# ANN.net
KiCad netlist of a schematic drawn in Altium Designer
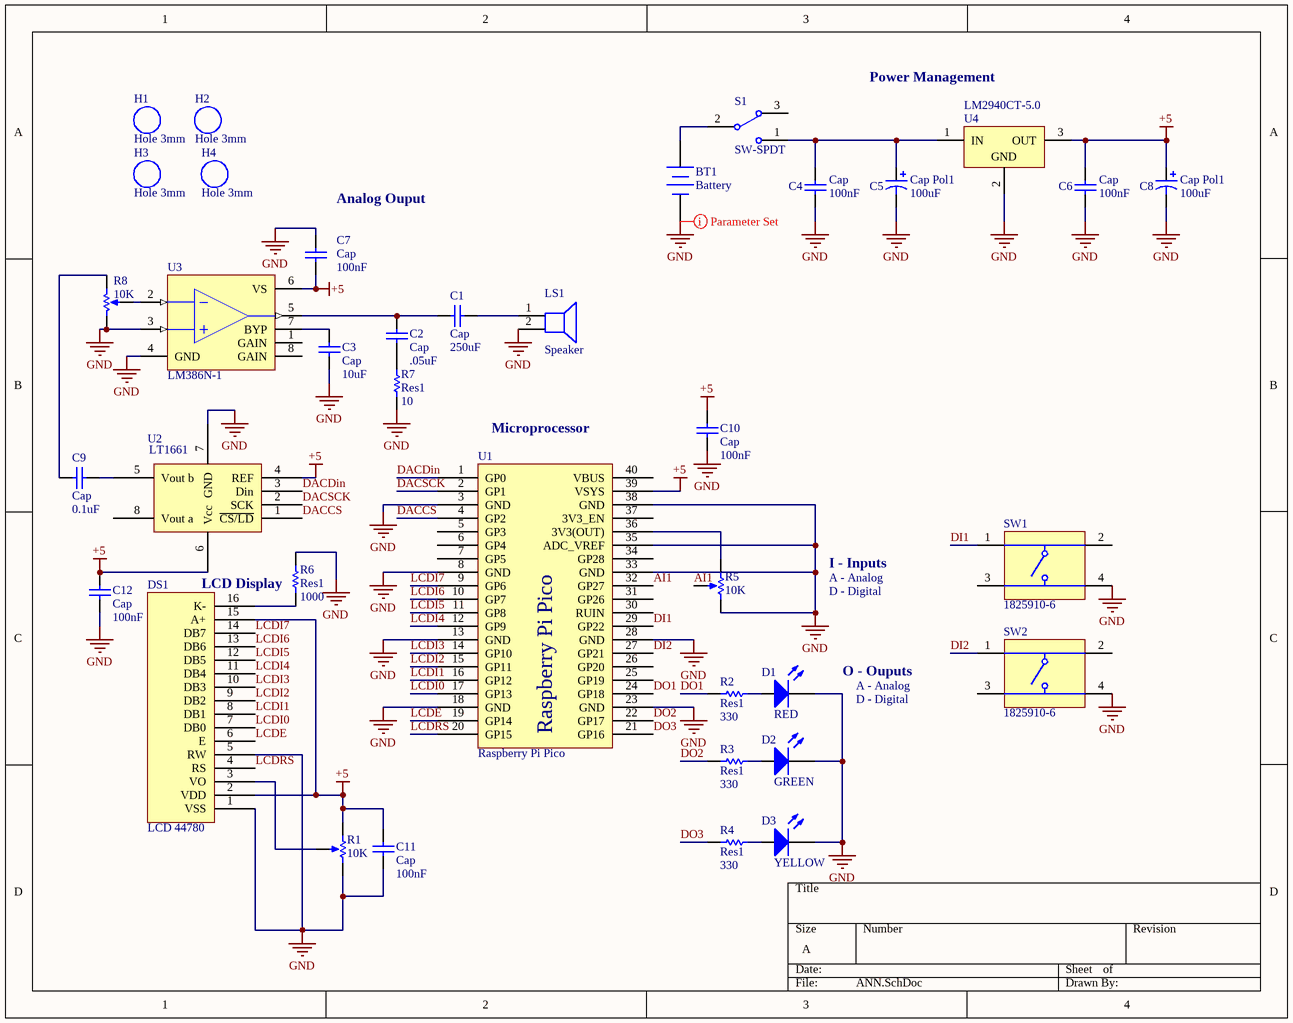
[diagram p0: ANN.SchDoc]

(export (version "E")
  (design (tool "Eeschema 10.0.6"))
  (components
    (comp (ref "BT1")
      (value "Battery")
      (footprint "BAT-2")
      (description "Multicell Battery")
      (fields (field (name "PUBLISHER") "Altium Limited"))
      (libsource (lib "Miscellaneous Devices") (part "Battery"))
    )
    (comp (ref "C1")
      (value "Cap")
      (footprint "RAD-0.3")
      (description "Capacitor")
      (fields (field (name "ALTIUM_VALUE") "250uF") (field (name "PUBLISHER") "Altium Limited"))
      (libsource (lib "Miscellaneous Devices") (part "Cap"))
    )
    (comp (ref "C2")
      (value "Cap")
      (footprint "RAD-0.3")
      (description "Capacitor")
      (fields (field (name "ALTIUM_VALUE") ".05uF") (field (name "PUBLISHER") "Altium Limited"))
      (libsource (lib "Miscellaneous Devices") (part "Cap"))
    )
    (comp (ref "C3")
      (value "Cap")
      (footprint "RAD-0.3")
      (description "Capacitor")
      (fields (field (name "ALTIUM_VALUE") "10uF") (field (name "PUBLISHER") "Altium Limited"))
      (libsource (lib "Miscellaneous Devices") (part "Cap"))
    )
    (comp (ref "C4")
      (value "Cap")
      (footprint "RAD-0.3")
      (description "Capacitor")
      (fields (field (name "ALTIUM_VALUE") "100nF") (field (name "PUBLISHER") "Altium Limited"))
      (libsource (lib "Miscellaneous Devices") (part "Cap"))
    )
    (comp (ref "C5")
      (value "Cap Pol1")
      (footprint "RB7.6-15")
      (description "Polarized Capacitor (Radial)")
      (fields (field (name "ALTIUM_VALUE") "100uF") (field (name "PUBLISHER") "Altium Limited"))
      (libsource (lib "Miscellaneous Devices") (part "Cap Pol1"))
    )
    (comp (ref "C6")
      (value "Cap")
      (footprint "RAD-0.3")
      (description "Capacitor")
      (fields (field (name "ALTIUM_VALUE") "100nF") (field (name "PUBLISHER") "Altium Limited"))
      (libsource (lib "Miscellaneous Devices") (part "Cap"))
    )
    (comp (ref "C7")
      (value "Cap")
      (footprint "RAD-0.3")
      (description "Capacitor")
      (fields (field (name "ALTIUM_VALUE") "100nF") (field (name "PUBLISHER") "Altium Limited"))
      (libsource (lib "Miscellaneous Devices") (part "Cap"))
    )
    (comp (ref "C8")
      (value "Cap Pol1")
      (footprint "RB7.6-15")
      (description "Polarized Capacitor (Radial)")
      (fields (field (name "ALTIUM_VALUE") "100uF") (field (name "PUBLISHER") "Altium Limited"))
      (libsource (lib "Miscellaneous Devices") (part "Cap Pol1"))
    )
    (comp (ref "C9")
      (value "Cap")
      (footprint "RAD-0.3")
      (description "Capacitor")
      (fields (field (name "ALTIUM_VALUE") "0.1uF") (field (name "PUBLISHER") "Altium Limited"))
      (libsource (lib "Miscellaneous Devices") (part "Cap"))
    )
    (comp (ref "C10")
      (value "Cap")
      (footprint "RAD-0.3")
      (description "Capacitor")
      (fields (field (name "ALTIUM_VALUE") "100nF") (field (name "PUBLISHER") "Altium Limited"))
      (libsource (lib "Miscellaneous Devices") (part "Cap"))
    )
    (comp (ref "C11")
      (value "Cap")
      (footprint "RAD-0.3")
      (description "Capacitor")
      (fields (field (name "ALTIUM_VALUE") "100nF") (field (name "PUBLISHER") "Altium Limited"))
      (libsource (lib "Miscellaneous Devices") (part "Cap"))
    )
    (comp (ref "C12")
      (value "Cap")
      (footprint "RAD-0.3")
      (description "Capacitor")
      (fields (field (name "ALTIUM_VALUE") "100nF") (field (name "PUBLISHER") "Altium Limited"))
      (libsource (lib "Miscellaneous Devices") (part "Cap"))
    )
    (comp (ref "D1")
      (value "RED")
      (footprint "LED-0")
      (description "Typical INFRARED GaAs LED")
      (fields (field (name "PUBLISHER") "Altium Limited"))
      (libsource (lib "Miscellaneous Devices") (part "LED0"))
    )
    (comp (ref "D2")
      (value "GREEN")
      (footprint "LED-0")
      (description "Typical INFRARED GaAs LED")
      (fields (field (name "PUBLISHER") "Altium Limited"))
      (libsource (lib "Miscellaneous Devices") (part "LED0"))
    )
    (comp (ref "D3")
      (value "YELLOW")
      (footprint "LED-0")
      (description "Typical INFRARED GaAs LED")
      (fields (field (name "PUBLISHER") "Altium Limited"))
      (libsource (lib "Miscellaneous Devices") (part "LED0"))
    )
    (comp (ref "DS1")
      (value "LCD 44780")
      (footprint "OLED 16x2")
      (libsource (lib "ECE Lib 22") (part "LCD 44780"))
    )
    (comp (ref "H1")
      (value "Hole 3mm")
      (footprint "Hole 3mm")
      (libsource (lib "ECE Lib 22") (part "Hole 3mm"))
    )
    (comp (ref "H2")
      (value "Hole 3mm")
      (footprint "Hole 3mm")
      (libsource (lib "ECE Lib 22") (part "Hole 3mm"))
    )
    (comp (ref "H3")
      (value "Hole 3mm")
      (footprint "Hole 3mm")
      (libsource (lib "ECE Lib 22") (part "Hole 3mm"))
    )
    (comp (ref "H4")
      (value "Hole 3mm")
      (footprint "Hole 3mm")
      (libsource (lib "ECE Lib 22") (part "Hole 3mm"))
    )
    (comp (ref "LS1")
      (value "Speaker")
      (footprint "PIN2")
      (description "Loudspeaker")
      (fields (field (name "PUBLISHER") "Altium Limited"))
      (libsource (lib "Miscellaneous Devices") (part "Speaker"))
    )
    (comp (ref "R1")
      (value "10K")
      (footprint "POT OFFSET 100_1")
      (description "Potentiometer")
      (fields (field (name "Comment") "RPot_2") (field (name "PUBLISHER") "Altium Limited"))
      (libsource (lib "ECE LIB new") (part "RPot_5"))
    )
    (comp (ref "R2")
      (value "Res1")
      (footprint "AXIAL-0.3")
      (description "Resistor")
      (fields (field (name "ALTIUM_VALUE") "330") (field (name "PUBLISHER") "Altium Limited"))
      (libsource (lib "Miscellaneous Devices") (part "Res1"))
    )
    (comp (ref "R3")
      (value "Res1")
      (footprint "AXIAL-0.3")
      (description "Resistor")
      (fields (field (name "ALTIUM_VALUE") "330") (field (name "PUBLISHER") "Altium Limited"))
      (libsource (lib "Miscellaneous Devices") (part "Res1"))
    )
    (comp (ref "R4")
      (value "Res1")
      (footprint "AXIAL-0.3")
      (description "Resistor")
      (fields (field (name "ALTIUM_VALUE") "330") (field (name "PUBLISHER") "Altium Limited"))
      (libsource (lib "Miscellaneous Devices") (part "Res1"))
    )
    (comp (ref "R5")
      (value "10K")
      (footprint "POT OFFSET 100_1")
      (description "Potentiometer")
      (fields (field (name "Comment") "RPot_2") (field (name "PUBLISHER") "Altium Limited"))
      (libsource (lib "ECE LIB new") (part "RPot_5"))
    )
    (comp (ref "R6")
      (value "Res1")
      (footprint "AXIAL-0.3")
      (description "Resistor")
      (fields (field (name "ALTIUM_VALUE") "1000") (field (name "PUBLISHER") "Altium Limited"))
      (libsource (lib "Miscellaneous Devices") (part "Res1"))
    )
    (comp (ref "R7")
      (value "Res1")
      (footprint "AXIAL-0.3")
      (description "Resistor")
      (fields (field (name "ALTIUM_VALUE") "10") (field (name "PUBLISHER") "Altium Limited"))
      (libsource (lib "Miscellaneous Devices") (part "Res1"))
    )
    (comp (ref "R8")
      (value "10K")
      (footprint "POT OFFSET 100_1")
      (description "Potentiometer")
      (fields (field (name "Comment") "RPot_2") (field (name "PUBLISHER") "Altium Limited"))
      (libsource (lib "ECE LIB new") (part "RPot_5"))
    )
    (comp (ref "S1")
      (value "SW-SPDT")
      (footprint "SW DPST jameco")
      (description "SPDT Subminiature Toggle Switch, Right Angle Mounting, Vertical Actuation")
      (fields (field (name "PUBLISHER") "Altium Limited"))
      (libsource (lib "ECE Lib 22") (part "SW-SPDT"))
    )
    (comp (ref "SW1")
      (value "1825910-6")
      (footprint "TECO-1825910-6_V")
      (description "Tact Switch, SPST-NO, 0.05 A, -35 to 85 degC, 4-Pin THD, RoHS, Bulk")
      (fields (field (name "MANUFACTURER") "TE Connectivity"))
      (libsource (lib "Altium Content Vault") (part "SW-SPST-4_A"))
    )
    (comp (ref "SW2")
      (value "1825910-6")
      (footprint "TECO-1825910-6_V")
      (description "Tact Switch, SPST-NO, 0.05 A, -35 to 85 degC, 4-Pin THD, RoHS, Bulk")
      (fields (field (name "MANUFACTURER") "TE Connectivity"))
      (libsource (lib "Altium Content Vault") (part "SW-SPST-4_A"))
    )
    (comp (ref "U1")
      (value "Raspberry Pi Pico")
      (footprint "Raspberry Pi Pico")
      (libsource (lib "ECE Lib 22") (part "Raspberry Pi Pico"))
    )
    (comp (ref "U2") (value "LT1661") (footprint "DIP-8") (libsource (lib "ECE LIB new") (part "LT1661")))
    (comp (ref "U3")
      (value "LM386N-1")
      (footprint "DIP-8")
      (description "Low-Voltage Audio Power Amplifier")
      (fields (field (name "PUBLISHER") "Altium Limited"))
      (libsource (lib "ECE LIB new") (part "LM386N-1"))
    )
    (comp (ref "U4")
      (value "LM2940CT-5.0")
      (footprint "T03B")
      (description "1A Low Dropout Regulator, 3-pin TO-220")
      (fields (field (name "MANUFACTURER") "National Semiconductor"))
      (libsource (lib "ECE Lib 22") (part "LM2940CT-5.0_1"))
    )
  )
  (nets
    (net (code "1") (name "+5") (class "Default")
      (node (ref "C10") (pin "2") (pinfunction "2_2") (pintype "passive"))
      (node (ref "C11") (pin "2") (pinfunction "2_2") (pintype "passive"))
      (node (ref "C12") (pin "2") (pinfunction "2_2") (pintype "passive"))
      (node (ref "C6") (pin "2") (pinfunction "2_2") (pintype "passive"))
      (node (ref "C7") (pin "2") (pinfunction "2_2") (pintype "passive"))
      (node (ref "C8") (pin "1") (pinfunction "1_1") (pintype "passive"))
      (node (ref "DS1") (pin "15") (pinfunction "A+_15") (pintype "passive"))
      (node (ref "DS1") (pin "2") (pinfunction "VDD_2") (pintype "passive"))
      (node (ref "R1") (pin "1") (pinfunction "TOP_1") (pintype "passive"))
      (node (ref "U1") (pin "39") (pinfunction "VSYS_39") (pintype "passive"))
      (node (ref "U2") (pin "4") (pinfunction "REF_4") (pintype "passive"))
      (node (ref "U2") (pin "6") (pinfunction "Vcc_6") (pintype "passive"))
      (node (ref "U3") (pin "6") (pinfunction "VS_6") (pintype "power_in"))
      (node (ref "U4") (pin "3") (pinfunction "OUT_3") (pintype "power_in"))
    )
    (net (code "2") (name "/AI1") (class "Default")
      (node (ref "R5") (pin "2") (pinfunction "TAP_2") (pintype "passive"))
      (node (ref "U1") (pin "32") (pinfunction "GP27_32") (pintype "passive"))
    )
    (net (code "3") (name "/DACCS") (class "Default")
      (node (ref "U1") (pin "4") (pinfunction "GP2_4") (pintype "passive"))
      (node (ref "U2") (pin "1") (pinfunction "~{CS/LD}_1") (pintype "passive"))
    )
    (net (code "4") (name "/DACDin") (class "Default")
      (node (ref "U1") (pin "1") (pinfunction "GP0_1") (pintype "passive"))
      (node (ref "U2") (pin "3") (pinfunction "Din_3") (pintype "passive"))
    )
    (net (code "5") (name "/DACSCK") (class "Default")
      (node (ref "U1") (pin "2") (pinfunction "GP1_2") (pintype "passive"))
      (node (ref "U2") (pin "2") (pinfunction "SCK_2") (pintype "passive"))
    )
    (net (code "6") (name "/DI1") (class "Default")
      (node (ref "SW1") (pin "1") (pinfunction "1_1") (pintype "passive"))
      (node (ref "U1") (pin "29") (pinfunction "GP22_29") (pintype "passive"))
    )
    (net (code "7") (name "/DI2") (class "Default")
      (node (ref "SW2") (pin "1") (pinfunction "1_1") (pintype "passive"))
      (node (ref "U1") (pin "27") (pinfunction "GP21_27") (pintype "passive"))
    )
    (net (code "8") (name "/DO1") (class "Default")
      (node (ref "R2") (pin "1") (pinfunction "1_1") (pintype "passive"))
      (node (ref "U1") (pin "24") (pinfunction "GP18_24") (pintype "passive"))
    )
    (net (code "9") (name "/DO2") (class "Default")
      (node (ref "R3") (pin "1") (pinfunction "1_1") (pintype "passive"))
      (node (ref "U1") (pin "22") (pinfunction "GP17_22") (pintype "passive"))
    )
    (net (code "10") (name "/DO3") (class "Default")
      (node (ref "R4") (pin "1") (pinfunction "1_1") (pintype "passive"))
      (node (ref "U1") (pin "21") (pinfunction "GP16_21") (pintype "passive"))
    )
    (net (code "11") (name "/LCDE") (class "Default")
      (node (ref "DS1") (pin "6") (pinfunction "E_6") (pintype "passive"))
      (node (ref "U1") (pin "19") (pinfunction "GP14_19") (pintype "passive"))
    )
    (net (code "12") (name "/LCDI0") (class "Default")
      (node (ref "DS1") (pin "7") (pinfunction "DB0_7") (pintype "passive"))
      (node (ref "U1") (pin "17") (pinfunction "GP13_17") (pintype "passive"))
    )
    (net (code "13") (name "/LCDI1") (class "Default")
      (node (ref "DS1") (pin "8") (pinfunction "DB1_8") (pintype "passive"))
      (node (ref "U1") (pin "16") (pinfunction "GP12_16") (pintype "passive"))
    )
    (net (code "14") (name "/LCDI2") (class "Default")
      (node (ref "DS1") (pin "9") (pinfunction "DB2_9") (pintype "passive"))
      (node (ref "U1") (pin "15") (pinfunction "GP11_15") (pintype "passive"))
    )
    (net (code "15") (name "/LCDI3") (class "Default")
      (node (ref "DS1") (pin "10") (pinfunction "DB3_10") (pintype "passive"))
      (node (ref "U1") (pin "14") (pinfunction "GP10_14") (pintype "passive"))
    )
    (net (code "16") (name "/LCDI4") (class "Default")
      (node (ref "DS1") (pin "11") (pinfunction "DB4_11") (pintype "passive"))
      (node (ref "U1") (pin "12") (pinfunction "GP9_12") (pintype "passive"))
    )
    (net (code "17") (name "/LCDI5") (class "Default")
      (node (ref "DS1") (pin "12") (pinfunction "DB5_12") (pintype "passive"))
      (node (ref "U1") (pin "11") (pinfunction "GP8_11") (pintype "passive"))
    )
    (net (code "18") (name "/LCDI6") (class "Default")
      (node (ref "DS1") (pin "13") (pinfunction "DB6_13") (pintype "passive"))
      (node (ref "U1") (pin "10") (pinfunction "GP7_10") (pintype "passive"))
    )
    (net (code "19") (name "/LCDI7") (class "Default")
      (node (ref "DS1") (pin "14") (pinfunction "DB7_14") (pintype "passive"))
      (node (ref "U1") (pin "9") (pinfunction "GP6_9") (pintype "passive"))
    )
    (net (code "20") (name "/LCDRS") (class "Default")
      (node (ref "DS1") (pin "4") (pinfunction "RS_4") (pintype "passive"))
      (node (ref "U1") (pin "20") (pinfunction "GP15_20") (pintype "passive"))
    )
    (net (code "21") (name "GND") (class "Default")
      (node (ref "BT1") (pin "2") (pinfunction "-_2") (pintype "passive"))
      (node (ref "C10") (pin "1") (pinfunction "1_1") (pintype "passive"))
      (node (ref "C11") (pin "1") (pinfunction "1_1") (pintype "passive"))
      (node (ref "C12") (pin "1") (pinfunction "1_1") (pintype "passive"))
      (node (ref "C3") (pin "1") (pinfunction "1_1") (pintype "passive"))
      (node (ref "C4") (pin "1") (pinfunction "1_1") (pintype "passive"))
      (node (ref "C5") (pin "2") (pinfunction "2_2") (pintype "passive"))
      (node (ref "C6") (pin "1") (pinfunction "1_1") (pintype "passive"))
      (node (ref "C7") (pin "1") (pinfunction "1_1") (pintype "passive"))
      (node (ref "C8") (pin "2") (pinfunction "2_2") (pintype "passive"))
      (node (ref "D1") (pin "2") (pinfunction "K_2") (pintype "passive"))
      (node (ref "D2") (pin "2") (pinfunction "K_2") (pintype "passive"))
      (node (ref "D3") (pin "2") (pinfunction "K_2") (pintype "passive"))
      (node (ref "DS1") (pin "1") (pinfunction "VSS_1") (pintype "passive"))
      (node (ref "DS1") (pin "5") (pinfunction "RW_5") (pintype "passive"))
      (node (ref "LS1") (pin "2") (pinfunction "2_2") (pintype "passive"))
      (node (ref "R1") (pin "3") (pinfunction "BOT_3") (pintype "passive"))
      (node (ref "R5") (pin "3") (pinfunction "BOT_3") (pintype "passive"))
      (node (ref "R6") (pin "2") (pinfunction "2_2") (pintype "passive"))
      (node (ref "R7") (pin "1") (pinfunction "1_1") (pintype "passive"))
      (node (ref "R8") (pin "3") (pinfunction "BOT_3") (pintype "passive"))
      (node (ref "SW1") (pin "4") (pinfunction "4_4") (pintype "passive"))
      (node (ref "SW2") (pin "4") (pinfunction "4_4") (pintype "passive"))
      (node (ref "U1") (pin "13") (pinfunction "GND_13") (pintype "passive"))
      (node (ref "U1") (pin "18") (pinfunction "GND_18") (pintype "passive"))
      (node (ref "U1") (pin "23") (pinfunction "GND_23") (pintype "passive"))
      (node (ref "U1") (pin "28") (pinfunction "GND_28") (pintype "passive"))
      (node (ref "U1") (pin "3") (pinfunction "GND_3") (pintype "passive"))
      (node (ref "U1") (pin "33") (pinfunction "GND_33") (pintype "passive"))
      (node (ref "U1") (pin "35") (pinfunction "ADC_VREF_35") (pintype "passive"))
      (node (ref "U1") (pin "38") (pinfunction "GND_38") (pintype "passive"))
      (node (ref "U1") (pin "8") (pinfunction "GND_8") (pintype "passive"))
      (node (ref "U2") (pin "7") (pinfunction "GND_7") (pintype "passive"))
      (node (ref "U3") (pin "3") (pinfunction "IN+_3") (pintype "input"))
      (node (ref "U3") (pin "4") (pinfunction "GND_4") (pintype "power_in"))
      (node (ref "U4") (pin "2") (pinfunction "GND_2") (pintype "power_in"))
    )
    (net (code "22") (name "Net-(BT1-+)") (class "Default")
      (node (ref "BT1") (pin "1") (pinfunction "+_1") (pintype "passive"))
      (node (ref "S1") (pin "2") (pinfunction "2_2") (pintype "passive"))
    )
    (net (code "23") (name "Net-(C1-Pad1)") (class "Default")
      (node (ref "C1") (pin "1") (pinfunction "1_1") (pintype "passive"))
      (node (ref "LS1") (pin "1") (pinfunction "1_1") (pintype "passive"))
    )
    (net (code "24") (name "Net-(C2-Pad1)") (class "Default")
      (node (ref "C2") (pin "1") (pinfunction "1_1") (pintype "passive"))
      (node (ref "R7") (pin "2") (pinfunction "2_2") (pintype "passive"))
    )
    (net (code "25") (name "Net-(D1-A)") (class "Default")
      (node (ref "D1") (pin "1") (pinfunction "A_1") (pintype "passive"))
      (node (ref "R2") (pin "2") (pinfunction "2_2") (pintype "passive"))
    )
    (net (code "26") (name "Net-(D2-A)") (class "Default")
      (node (ref "D2") (pin "1") (pinfunction "A_1") (pintype "passive"))
      (node (ref "R3") (pin "2") (pinfunction "2_2") (pintype "passive"))
    )
    (net (code "27") (name "Net-(D3-A)") (class "Default")
      (node (ref "D3") (pin "1") (pinfunction "A_1") (pintype "passive"))
      (node (ref "R4") (pin "2") (pinfunction "2_2") (pintype "passive"))
    )
    (net (code "28") (name "Net-(DS1-K-)") (class "Default")
      (node (ref "DS1") (pin "16") (pinfunction "K-_16") (pintype "passive"))
      (node (ref "R6") (pin "1") (pinfunction "1_1") (pintype "passive"))
    )
    (net (code "29") (name "Net-(DS1-VO)") (class "Default")
      (node (ref "DS1") (pin "3") (pinfunction "VO_3") (pintype "passive"))
      (node (ref "R1") (pin "2") (pinfunction "TAP_2") (pintype "passive"))
    )
    (net (code "30") (name "Net-(R5-TOP)") (class "Default")
      (node (ref "R5") (pin "1") (pinfunction "TOP_1") (pintype "passive"))
      (node (ref "U1") (pin "36") (pinfunction "3V3(OUT)_36") (pintype "passive"))
    )
    (net (code "31") (name "Net-(R8-TAP)") (class "Default")
      (node (ref "R8") (pin "2") (pinfunction "TAP_2") (pintype "passive"))
      (node (ref "U3") (pin "2") (pinfunction "IN-_2") (pintype "input"))
    )
    (net (code "32") (name "Net-(R8-TOP)") (class "Default")
      (node (ref "C9") (pin "2") (pinfunction "2_2") (pintype "passive"))
      (node (ref "R8") (pin "1") (pinfunction "TOP_1") (pintype "passive"))
    )
    (net (code "33") (name "Net-(U2-Vout_b)") (class "Default")
      (node (ref "C9") (pin "1") (pinfunction "1_1") (pintype "passive"))
      (node (ref "U2") (pin "5") (pinfunction "Vout_b_5") (pintype "passive"))
    )
    (net (code "34") (name "Net-(U3-BYP)") (class "Default")
      (node (ref "C3") (pin "2") (pinfunction "2_2") (pintype "passive"))
      (node (ref "U3") (pin "7") (pinfunction "BYP_7") (pintype "passive"))
    )
    (net (code "35") (name "Net-(U3-OUT)") (class "Default")
      (node (ref "C1") (pin "2") (pinfunction "2_2") (pintype "passive"))
      (node (ref "C2") (pin "2") (pinfunction "2_2") (pintype "passive"))
      (node (ref "U3") (pin "5") (pinfunction "OUT_5") (pintype "output"))
    )
    (net (code "36") (name "Net-(U4-IN)") (class "Default")
      (node (ref "C4") (pin "2") (pinfunction "2_2") (pintype "passive"))
      (node (ref "C5") (pin "1") (pinfunction "1_1") (pintype "passive"))
      (node (ref "S1") (pin "1") (pinfunction "1_1") (pintype "passive"))
      (node (ref "U4") (pin "1") (pinfunction "IN_1") (pintype "power_in"))
    )
    (net (code "37") (name "unconnected-(S1-Pad3)") (class "Default")
      (node (ref "S1") (pin "3") (pinfunction "3_3") (pintype "passive"))
    )
    (net (code "38") (name "unconnected-(SW1-Pad2)") (class "Default")
      (node (ref "SW1") (pin "2") (pinfunction "2_2") (pintype "passive"))
    )
    (net (code "39") (name "unconnected-(SW1-Pad3)") (class "Default")
      (node (ref "SW1") (pin "3") (pinfunction "3_3") (pintype "passive"))
    )
    (net (code "40") (name "unconnected-(SW2-Pad2)") (class "Default")
      (node (ref "SW2") (pin "2") (pinfunction "2_2") (pintype "passive"))
    )
    (net (code "41") (name "unconnected-(SW2-Pad3)") (class "Default")
      (node (ref "SW2") (pin "3") (pinfunction "3_3") (pintype "passive"))
    )
    (net (code "42") (name "unconnected-(U1-3V3_EN-Pad37)") (class "Default")
      (node (ref "U1") (pin "37") (pinfunction "3V3_EN_37") (pintype "passive"))
    )
    (net (code "43") (name "unconnected-(U1-GP3-Pad5)") (class "Default")
      (node (ref "U1") (pin "5") (pinfunction "GP3_5") (pintype "passive"))
    )
    (net (code "44") (name "unconnected-(U1-GP4-Pad6)") (class "Default")
      (node (ref "U1") (pin "6") (pinfunction "GP4_6") (pintype "passive"))
    )
    (net (code "45") (name "unconnected-(U1-GP5-Pad7)") (class "Default")
      (node (ref "U1") (pin "7") (pinfunction "GP5_7") (pintype "passive"))
    )
    (net (code "46") (name "unconnected-(U1-GP19-Pad25)") (class "Default")
      (node (ref "U1") (pin "25") (pinfunction "GP19_25") (pintype "passive"))
    )
    (net (code "47") (name "unconnected-(U1-GP20-Pad26)") (class "Default")
      (node (ref "U1") (pin "26") (pinfunction "GP20_26") (pintype "passive"))
    )
    (net (code "48") (name "unconnected-(U1-GP26-Pad31)") (class "Default")
      (node (ref "U1") (pin "31") (pinfunction "GP26_31") (pintype "passive"))
    )
    (net (code "49") (name "unconnected-(U1-GP28-Pad34)") (class "Default")
      (node (ref "U1") (pin "34") (pinfunction "GP28_34") (pintype "passive"))
    )
    (net (code "50") (name "unconnected-(U1-RUIN-Pad30)") (class "Default")
      (node (ref "U1") (pin "30") (pinfunction "RUIN_30") (pintype "passive"))
    )
    (net (code "51") (name "unconnected-(U1-VBUS-Pad40)") (class "Default")
      (node (ref "U1") (pin "40") (pinfunction "VBUS_40") (pintype "passive"))
    )
    (net (code "52") (name "unconnected-(U2-Vout_a-Pad8)") (class "Default")
      (node (ref "U2") (pin "8") (pinfunction "Vout_a_8") (pintype "passive"))
    )
    (net (code "53") (name "unconnected-(U3-GAIN-Pad1)") (class "Default")
      (node (ref "U3") (pin "1") (pinfunction "GAIN_1") (pintype "passive"))
    )
    (net (code "54") (name "unconnected-(U3-GAIN-Pad8)") (class "Default")
      (node (ref "U3") (pin "8") (pinfunction "GAIN_8") (pintype "passive"))
    )
  )
)
